# Z80-Clock-And-Reset-1-1.net
KiCad netlist of a schematic drawn in EAGLE
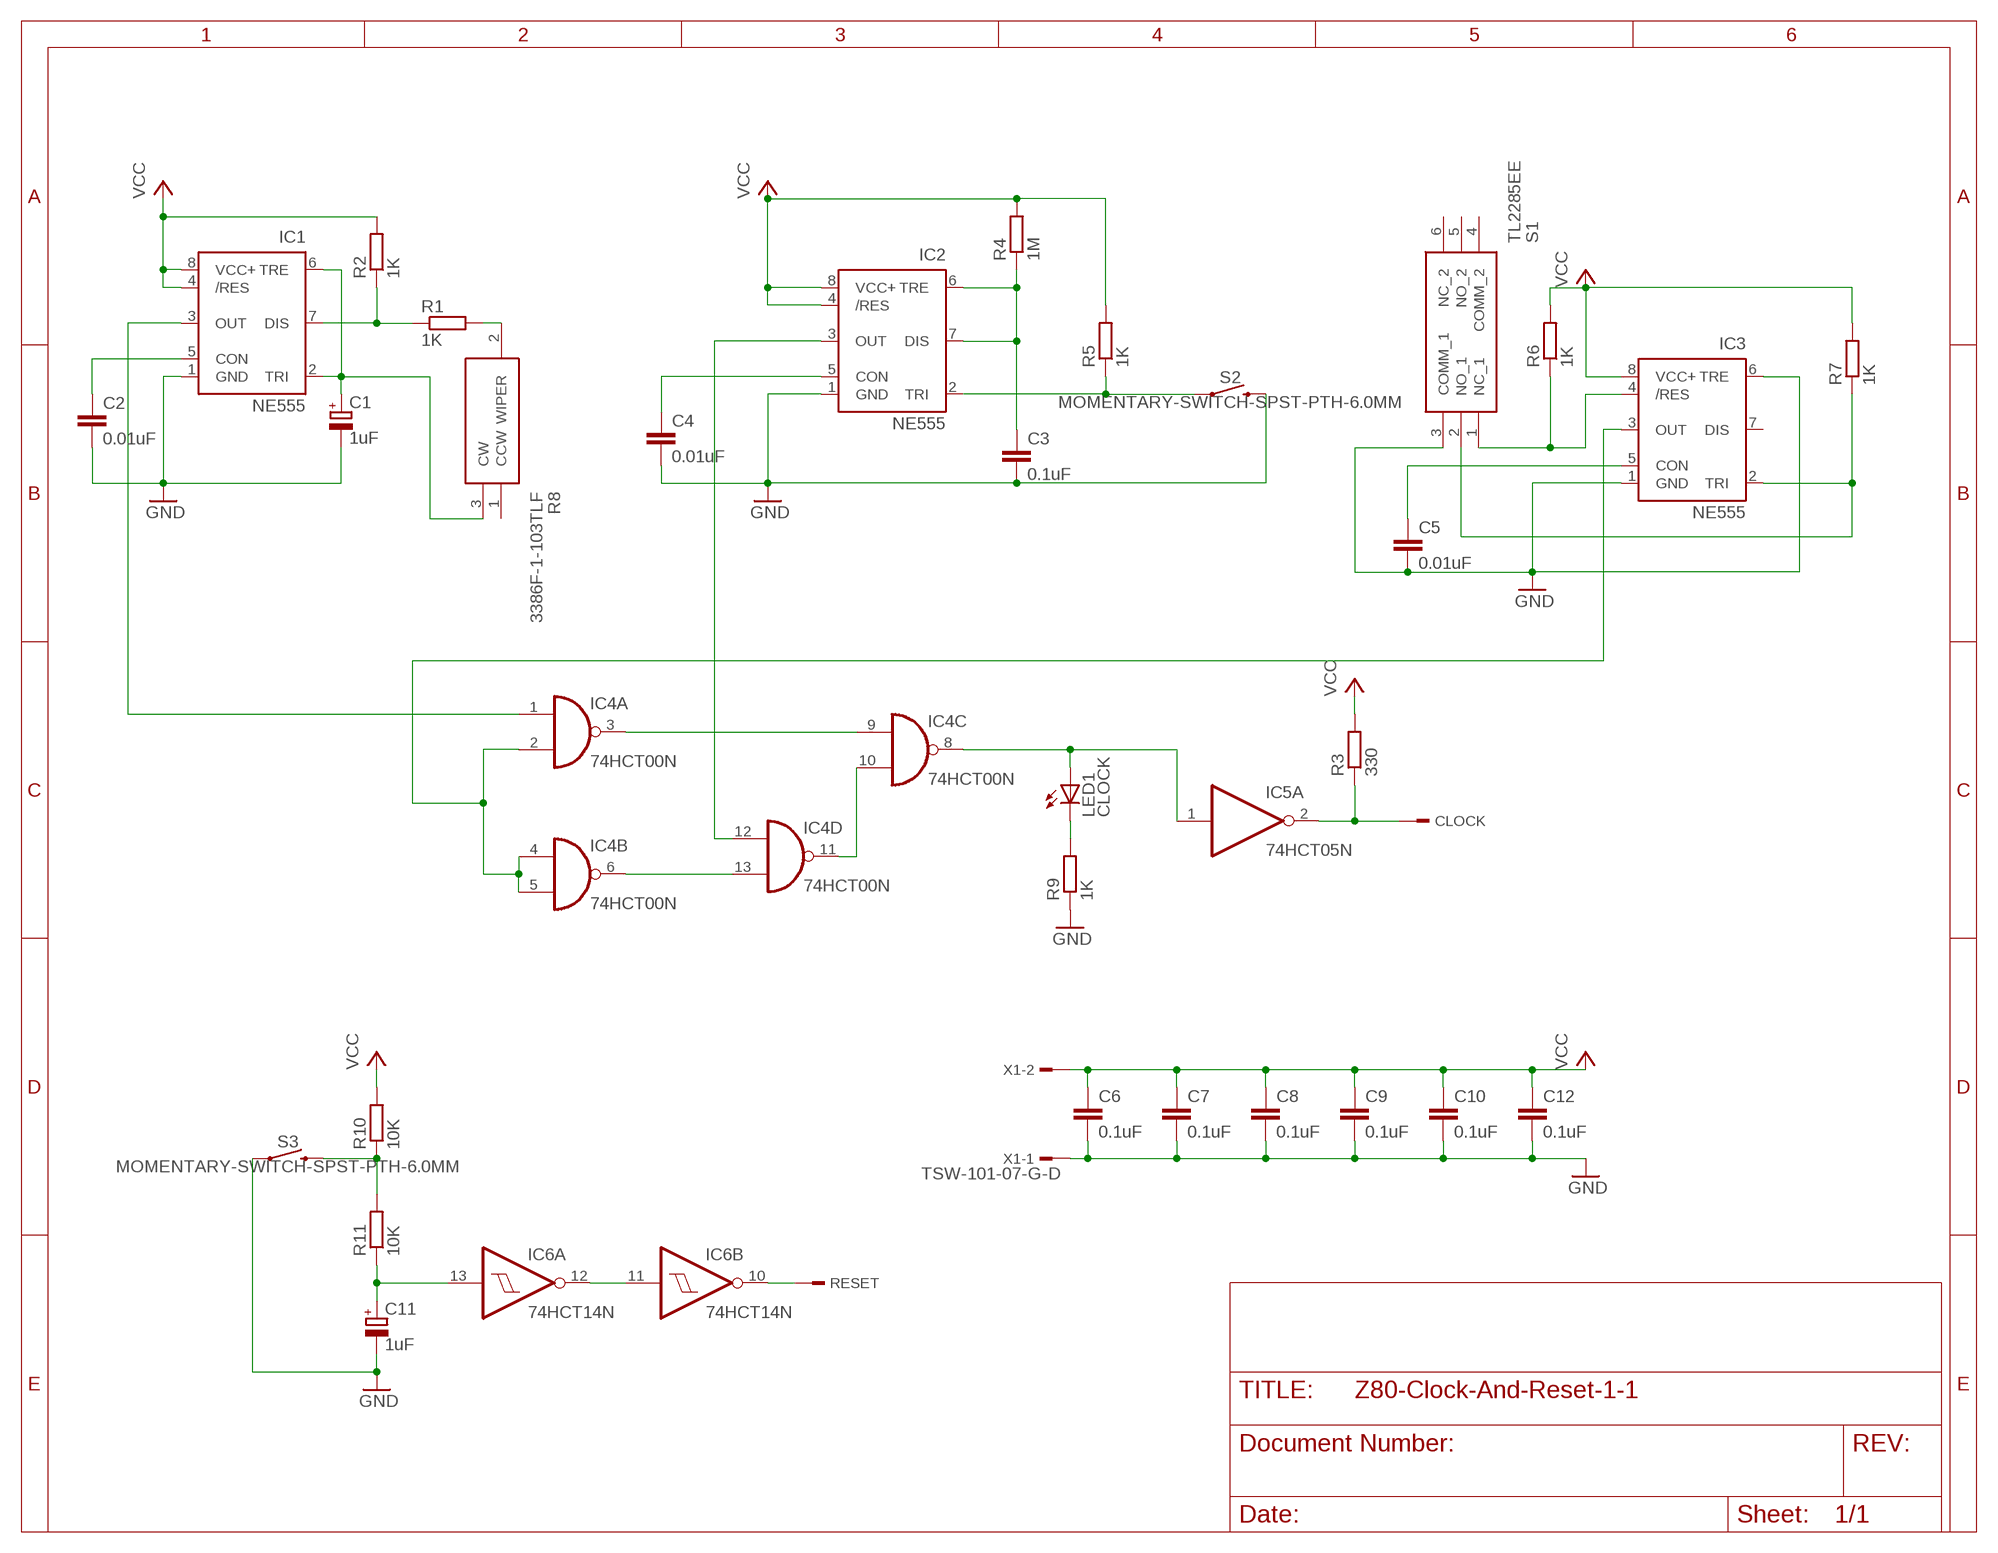
[diagram p0: schematic, sheet 1]

(export (version "E")
  (design (tool "Eeschema 10.0.6"))
  (components
    (comp (ref "C1")
      (value "1uF")
      (footprint "eagle-import:E2,5-6E")
      (libsource (lib "eagle-import") (part "CPOL-EUE2,5-6E"))
    )
    (comp (ref "C2")
      (value "0.01uF")
      (footprint "eagle-import:C050-025X075")
      (libsource (lib "eagle-import") (part "C-EU050-025X075"))
    )
    (comp (ref "C3")
      (value "0.1uF")
      (footprint "eagle-import:C050-025X075")
      (libsource (lib "eagle-import") (part "C-EU050-025X075"))
    )
    (comp (ref "C4")
      (value "0.01uF")
      (footprint "eagle-import:C050-025X075")
      (libsource (lib "eagle-import") (part "C-EU050-025X075"))
    )
    (comp (ref "C5")
      (value "0.01uF")
      (footprint "eagle-import:C050-025X075")
      (libsource (lib "eagle-import") (part "C-EU050-025X075"))
    )
    (comp (ref "C6")
      (value "0.1uF")
      (footprint "eagle-import:C050-025X075")
      (libsource (lib "eagle-import") (part "C-EU050-025X075"))
    )
    (comp (ref "C7")
      (value "0.1uF")
      (footprint "eagle-import:C050-025X075")
      (libsource (lib "eagle-import") (part "C-EU050-025X075"))
    )
    (comp (ref "C8")
      (value "0.1uF")
      (footprint "eagle-import:C050-025X075")
      (libsource (lib "eagle-import") (part "C-EU050-025X075"))
    )
    (comp (ref "C9")
      (value "0.1uF")
      (footprint "eagle-import:C050-025X075")
      (libsource (lib "eagle-import") (part "C-EU050-025X075"))
    )
    (comp (ref "C10")
      (value "0.1uF")
      (footprint "eagle-import:C050-025X075")
      (libsource (lib "eagle-import") (part "C-EU050-025X075"))
    )
    (comp (ref "C11")
      (value "1uF")
      (footprint "eagle-import:E2,5-6E")
      (libsource (lib "eagle-import") (part "CPOL-EUE2,5-6E"))
    )
    (comp (ref "C12")
      (value "0.1uF")
      (footprint "eagle-import:C050-025X075")
      (libsource (lib "eagle-import") (part "C-EU050-025X075"))
    )
    (comp (ref "CLOCK")
      (value "TSW-101-07-G-S")
      (footprint "eagle-import:TSW-101-XX-G-S")
      (fields (field (name "MF") "Samtec Inc."))
      (libsource (lib "eagle-import") (part "TSW-101--G-S07"))
    )
    (comp (ref "IC1")
      (value "NE555")
      (footprint "eagle-import:DIL-08")
      (fields (field (name "MF") "Arrow Electronics") (field (name "MPN") "NE555N"))
      (libsource (lib "eagle-import") (part "NE555"))
    )
    (comp (ref "IC2")
      (value "NE555")
      (footprint "eagle-import:DIL-08")
      (fields (field (name "MF") "Arrow Electronics") (field (name "MPN") "NE555N"))
      (libsource (lib "eagle-import") (part "NE555"))
    )
    (comp (ref "IC3")
      (value "NE555")
      (footprint "eagle-import:DIL-08")
      (fields (field (name "MF") "Arrow Electronics") (field (name "MPN") "NE555N"))
      (libsource (lib "eagle-import") (part "NE555"))
    )
    (comp (ref "IC4")
      (value "74HCT00N")
      (footprint "eagle-import:DIL14")
      (libsource (lib "eagle-import") (part "7400NHCT"))
    )
    (comp (ref "IC5")
      (value "74HCT05N")
      (footprint "eagle-import:DIL14")
      (libsource (lib "eagle-import") (part "7405NHCT"))
    )
    (comp (ref "IC6")
      (value "74HCT14N")
      (footprint "eagle-import:DIL14")
      (libsource (lib "eagle-import") (part "7414NHCT"))
    )
    (comp (ref "LED1")
      (value "CLOCK")
      (footprint "eagle-import:LED3MM")
      (libsource (lib "eagle-import") (part "LED3MM"))
    )
    (comp (ref "R1")
      (value "1K")
      (footprint "eagle-import:0207_10")
      (libsource (lib "eagle-import") (part "R-EU_0207/10"))
    )
    (comp (ref "R2")
      (value "1K")
      (footprint "eagle-import:0207_10")
      (libsource (lib "eagle-import") (part "R-EU_0207/10"))
    )
    (comp (ref "R3")
      (value "330")
      (footprint "eagle-import:0207_10")
      (libsource (lib "eagle-import") (part "R-EU_0207/10"))
    )
    (comp (ref "R4")
      (value "1M")
      (footprint "eagle-import:0207_10")
      (libsource (lib "eagle-import") (part "R-EU_0207/10"))
    )
    (comp (ref "R5")
      (value "1K")
      (footprint "eagle-import:0207_10")
      (libsource (lib "eagle-import") (part "R-EU_0207/10"))
    )
    (comp (ref "R6")
      (value "1K")
      (footprint "eagle-import:0207_10")
      (libsource (lib "eagle-import") (part "R-EU_0207/10"))
    )
    (comp (ref "R7")
      (value "1K")
      (footprint "eagle-import:0207_10")
      (libsource (lib "eagle-import") (part "R-EU_0207/10"))
    )
    (comp (ref "R8")
      (value "3386F-1-103TLF")
      (footprint "eagle-import:3386F1103TLF")
      (fields (field (name "MOUSER_PART_NUMBER") "652-3386F-1-103TLF"))
      (libsource (lib "eagle-import") (part "3386F-1-103TLF"))
    )
    (comp (ref "R9")
      (value "1K")
      (footprint "eagle-import:0207_10")
      (libsource (lib "eagle-import") (part "R-EU_0207/10"))
    )
    (comp (ref "R10")
      (value "10K")
      (footprint "eagle-import:0207_10")
      (libsource (lib "eagle-import") (part "R-EU_0207/10"))
    )
    (comp (ref "R11")
      (value "10K")
      (footprint "eagle-import:0207_10")
      (libsource (lib "eagle-import") (part "R-EU_0207/10"))
    )
    (comp (ref "RESET")
      (value "TSW-101-07-G-S")
      (footprint "eagle-import:TSW-101-XX-G-S")
      (fields (field (name "MF") "Samtec Inc."))
      (libsource (lib "eagle-import") (part "TSW-101--G-S07"))
    )
    (comp (ref "S1")
      (value "TL2285EE")
      (footprint "eagle-import:TL2285EE")
      (fields (field (name "MOUSER_PART_NUMBER") "612-TL2285EE"))
      (libsource (lib "eagle-import") (part "TL2285EE"))
    )
    (comp (ref "S2")
      (value "MOMENTARY-SWITCH-SPST-PTH-6.0MM")
      (footprint "eagle-import:TACTILE_SWITCH_PTH_6.0MM")
      (libsource (lib "eagle-import") (part "MOMENTARY-SWITCH-SPST-PTH-6.0MM"))
    )
    (comp (ref "S3")
      (value "MOMENTARY-SWITCH-SPST-PTH-6.0MM")
      (footprint "eagle-import:TACTILE_SWITCH_PTH_6.0MM")
      (libsource (lib "eagle-import") (part "MOMENTARY-SWITCH-SPST-PTH-6.0MM"))
    )
    (comp (ref "X1")
      (value "TSW-101-07-G-D")
      (footprint "eagle-import:TSW-101-XX-G-D")
      (fields (field (name "MF") "Samtec Inc."))
      (libsource (lib "eagle-import") (part "TSW-101--G-D07"))
    )
  )
  (nets
    (net (code "1") (name "GND") (class "Default")
      (node (ref "C1") (pin "-") (pinfunction "-_-") (pintype "passive"))
      (node (ref "C10") (pin "2") (pinfunction "2_2") (pintype "passive"))
      (node (ref "C11") (pin "-") (pinfunction "-_-") (pintype "passive"))
      (node (ref "C12") (pin "2") (pinfunction "2_2") (pintype "passive"))
      (node (ref "C2") (pin "2") (pinfunction "2_2") (pintype "passive"))
      (node (ref "C3") (pin "2") (pinfunction "2_2") (pintype "passive"))
      (node (ref "C4") (pin "2") (pinfunction "2_2") (pintype "passive"))
      (node (ref "C5") (pin "2") (pinfunction "2_2") (pintype "passive"))
      (node (ref "C6") (pin "2") (pinfunction "2_2") (pintype "passive"))
      (node (ref "C7") (pin "2") (pinfunction "2_2") (pintype "passive"))
      (node (ref "C8") (pin "2") (pinfunction "2_2") (pintype "passive"))
      (node (ref "C9") (pin "2") (pinfunction "2_2") (pintype "passive"))
      (node (ref "IC1") (pin "1") (pinfunction "GND_1") (pintype "power_in"))
      (node (ref "IC2") (pin "1") (pinfunction "GND_1") (pintype "power_in"))
      (node (ref "IC3") (pin "1") (pinfunction "GND_1") (pintype "power_in"))
      (node (ref "IC3") (pin "6") (pinfunction "TRE_6") (pintype "input"))
      (node (ref "R9") (pin "1") (pinfunction "1_1") (pintype "passive"))
      (node (ref "S1") (pin "3") (pinfunction "COMM_1_3") (pintype "bidirectional"))
      (node (ref "S2") (pin "3") (pinfunction "2_3") (pintype "passive"))
      (node (ref "S3") (pin "1") (pinfunction "1_1") (pintype "passive"))
      (node (ref "X1") (pin "1") (pinfunction "1_1") (pintype "passive"))
    )
    (net (code "2") (name "Net-(IC1-CON)") (class "Default")
      (node (ref "C2") (pin "1") (pinfunction "1_1") (pintype "passive"))
      (node (ref "IC1") (pin "5") (pinfunction "CON_5") (pintype "input"))
    )
    (net (code "3") (name "Net-(IC1-DIS)") (class "Default")
      (node (ref "IC1") (pin "7") (pinfunction "DIS_7") (pintype "input"))
      (node (ref "R1") (pin "1") (pinfunction "1_1") (pintype "passive"))
      (node (ref "R2") (pin "1") (pinfunction "1_1") (pintype "passive"))
    )
    (net (code "4") (name "Net-(IC1-OUT)") (class "Default")
      (node (ref "IC1") (pin "3") (pinfunction "OUT_3") (pintype "output"))
      (node (ref "IC4") (pin "1") (pinfunction "I0_1") (pintype "input"))
    )
    (net (code "5") (name "Net-(IC1-TRE)") (class "Default")
      (node (ref "C1") (pin "+") (pinfunction "+_+") (pintype "passive"))
      (node (ref "IC1") (pin "2") (pinfunction "TRI_2") (pintype "input"))
      (node (ref "IC1") (pin "6") (pinfunction "TRE_6") (pintype "input"))
      (node (ref "R8") (pin "3") (pinfunction "CW_3") (pintype "bidirectional"))
    )
    (net (code "6") (name "Net-(IC2-CON)") (class "Default")
      (node (ref "C4") (pin "1") (pinfunction "1_1") (pintype "passive"))
      (node (ref "IC2") (pin "5") (pinfunction "CON_5") (pintype "input"))
    )
    (net (code "7") (name "Net-(IC2-DIS)") (class "Default")
      (node (ref "C3") (pin "1") (pinfunction "1_1") (pintype "passive"))
      (node (ref "IC2") (pin "6") (pinfunction "TRE_6") (pintype "input"))
      (node (ref "IC2") (pin "7") (pinfunction "DIS_7") (pintype "input"))
      (node (ref "R4") (pin "1") (pinfunction "1_1") (pintype "passive"))
    )
    (net (code "8") (name "Net-(IC2-OUT)") (class "Default")
      (node (ref "IC2") (pin "3") (pinfunction "OUT_3") (pintype "output"))
      (node (ref "IC4") (pin "12") (pinfunction "I0_12") (pintype "input"))
    )
    (net (code "9") (name "Net-(IC2-TRI)") (class "Default")
      (node (ref "IC2") (pin "2") (pinfunction "TRI_2") (pintype "input"))
      (node (ref "R5") (pin "1") (pinfunction "1_1") (pintype "passive"))
      (node (ref "S2") (pin "1") (pinfunction "1_1") (pintype "passive"))
    )
    (net (code "10") (name "Net-(IC3-CON)") (class "Default")
      (node (ref "C5") (pin "1") (pinfunction "1_1") (pintype "passive"))
      (node (ref "IC3") (pin "5") (pinfunction "CON_5") (pintype "input"))
    )
    (net (code "11") (name "Net-(IC3-OUT)") (class "Default")
      (node (ref "IC3") (pin "3") (pinfunction "OUT_3") (pintype "output"))
      (node (ref "IC4") (pin "2") (pinfunction "I1_2") (pintype "input"))
      (node (ref "IC4") (pin "4") (pinfunction "I0_4") (pintype "input"))
      (node (ref "IC4") (pin "5") (pinfunction "I1_5") (pintype "input"))
    )
    (net (code "12") (name "Net-(IC3-TRI)") (class "Default")
      (node (ref "IC3") (pin "2") (pinfunction "TRI_2") (pintype "input"))
      (node (ref "R7") (pin "1") (pinfunction "1_1") (pintype "passive"))
      (node (ref "S1") (pin "2") (pinfunction "NO_1_2") (pintype "bidirectional"))
    )
    (net (code "13") (name "Net-(IC3-{slash}RES)") (class "Default")
      (node (ref "IC3") (pin "4") (pinfunction "/RES_4") (pintype "input"))
      (node (ref "R6") (pin "1") (pinfunction "1_1") (pintype "passive"))
      (node (ref "S1") (pin "1") (pinfunction "NC_1_1") (pintype "bidirectional"))
    )
    (net (code "14") (name "Net-(IC4A-O)") (class "Default")
      (node (ref "IC4") (pin "3") (pinfunction "O_3") (pintype "output"))
      (node (ref "IC4") (pin "9") (pinfunction "I0_9") (pintype "input"))
    )
    (net (code "15") (name "Net-(IC4B-O)") (class "Default")
      (node (ref "IC4") (pin "13") (pinfunction "I1_13") (pintype "input"))
      (node (ref "IC4") (pin "6") (pinfunction "O_6") (pintype "output"))
    )
    (net (code "16") (name "Net-(IC4C-I1)") (class "Default")
      (node (ref "IC4") (pin "10") (pinfunction "I1_10") (pintype "input"))
      (node (ref "IC4") (pin "11") (pinfunction "O_11") (pintype "output"))
    )
    (net (code "17") (name "Net-(IC4C-O)") (class "Default")
      (node (ref "IC4") (pin "8") (pinfunction "O_8") (pintype "output"))
      (node (ref "IC5") (pin "1") (pinfunction "I_1") (pintype "input"))
      (node (ref "LED1") (pin "A") (pinfunction "A_A") (pintype "passive"))
    )
    (net (code "18") (name "Net-(IC5A-O)") (class "Default")
      (node (ref "CLOCK") (pin "1") (pinfunction "1_1") (pintype "passive"))
      (node (ref "IC5") (pin "2") (pinfunction "O_2") (pintype "open_collector"))
      (node (ref "R3") (pin "1") (pinfunction "1_1") (pintype "passive"))
    )
    (net (code "19") (name "Net-(IC6A-I)") (class "Default")
      (node (ref "C11") (pin "+") (pinfunction "+_+") (pintype "passive"))
      (node (ref "IC6") (pin "13") (pinfunction "I_13") (pintype "input"))
      (node (ref "R11") (pin "1") (pinfunction "1_1") (pintype "passive"))
    )
    (net (code "20") (name "Net-(IC6A-O)") (class "Default")
      (node (ref "IC6") (pin "11") (pinfunction "I_11") (pintype "input"))
      (node (ref "IC6") (pin "12") (pinfunction "O_12") (pintype "output"))
    )
    (net (code "21") (name "Net-(IC6B-O)") (class "Default")
      (node (ref "IC6") (pin "10") (pinfunction "O_10") (pintype "output"))
      (node (ref "RESET") (pin "1") (pinfunction "1_1") (pintype "passive"))
    )
    (net (code "22") (name "Net-(LED1-C)") (class "Default")
      (node (ref "LED1") (pin "K") (pinfunction "C_K") (pintype "passive"))
      (node (ref "R9") (pin "2") (pinfunction "2_2") (pintype "passive"))
    )
    (net (code "23") (name "Net-(R8-WIPER)") (class "Default")
      (node (ref "R1") (pin "2") (pinfunction "2_2") (pintype "passive"))
      (node (ref "R8") (pin "2") (pinfunction "WIPER_2") (pintype "bidirectional"))
    )
    (net (code "24") (name "Net-(S3-2)") (class "Default")
      (node (ref "R10") (pin "1") (pinfunction "1_1") (pintype "passive"))
      (node (ref "R11") (pin "2") (pinfunction "2_2") (pintype "passive"))
      (node (ref "S3") (pin "3") (pinfunction "2_3") (pintype "passive"))
    )
    (net (code "25") (name "VCC") (class "Default")
      (node (ref "C10") (pin "1") (pinfunction "1_1") (pintype "passive"))
      (node (ref "C12") (pin "1") (pinfunction "1_1") (pintype "passive"))
      (node (ref "C6") (pin "1") (pinfunction "1_1") (pintype "passive"))
      (node (ref "C7") (pin "1") (pinfunction "1_1") (pintype "passive"))
      (node (ref "C8") (pin "1") (pinfunction "1_1") (pintype "passive"))
      (node (ref "C9") (pin "1") (pinfunction "1_1") (pintype "passive"))
      (node (ref "IC1") (pin "4") (pinfunction "/RES_4") (pintype "input"))
      (node (ref "IC1") (pin "8") (pinfunction "VCC+_8") (pintype "power_in"))
      (node (ref "IC2") (pin "4") (pinfunction "/RES_4") (pintype "input"))
      (node (ref "IC2") (pin "8") (pinfunction "VCC+_8") (pintype "power_in"))
      (node (ref "IC3") (pin "8") (pinfunction "VCC+_8") (pintype "power_in"))
      (node (ref "R10") (pin "2") (pinfunction "2_2") (pintype "passive"))
      (node (ref "R2") (pin "2") (pinfunction "2_2") (pintype "passive"))
      (node (ref "R3") (pin "2") (pinfunction "2_2") (pintype "passive"))
      (node (ref "R4") (pin "2") (pinfunction "2_2") (pintype "passive"))
      (node (ref "R5") (pin "2") (pinfunction "2_2") (pintype "passive"))
      (node (ref "R6") (pin "2") (pinfunction "2_2") (pintype "passive"))
      (node (ref "R7") (pin "2") (pinfunction "2_2") (pintype "passive"))
      (node (ref "X1") (pin "2") (pinfunction "1_2") (pintype "passive"))
    )
    (net (code "26") (name "unconnected-(IC3-DIS-Pad7)") (class "Default")
      (node (ref "IC3") (pin "7") (pinfunction "DIS_7") (pintype "input"))
    )
    (net (code "27") (name "unconnected-(R8-CCW-Pad1)") (class "Default")
      (node (ref "R8") (pin "1") (pinfunction "CCW_1") (pintype "bidirectional"))
    )
    (net (code "28") (name "unconnected-(S1-COMM_2-Pad4)") (class "Default")
      (node (ref "S1") (pin "4") (pinfunction "COMM_2_4") (pintype "bidirectional"))
    )
    (net (code "29") (name "unconnected-(S1-NC_2-Pad6)") (class "Default")
      (node (ref "S1") (pin "6") (pinfunction "NC_2_6") (pintype "bidirectional"))
    )
    (net (code "30") (name "unconnected-(S1-NO_2-Pad5)") (class "Default")
      (node (ref "S1") (pin "5") (pinfunction "NO_2_5") (pintype "bidirectional"))
    )
  )
)
